# Power.net
KiCad netlist of a schematic drawn in Altium Designer
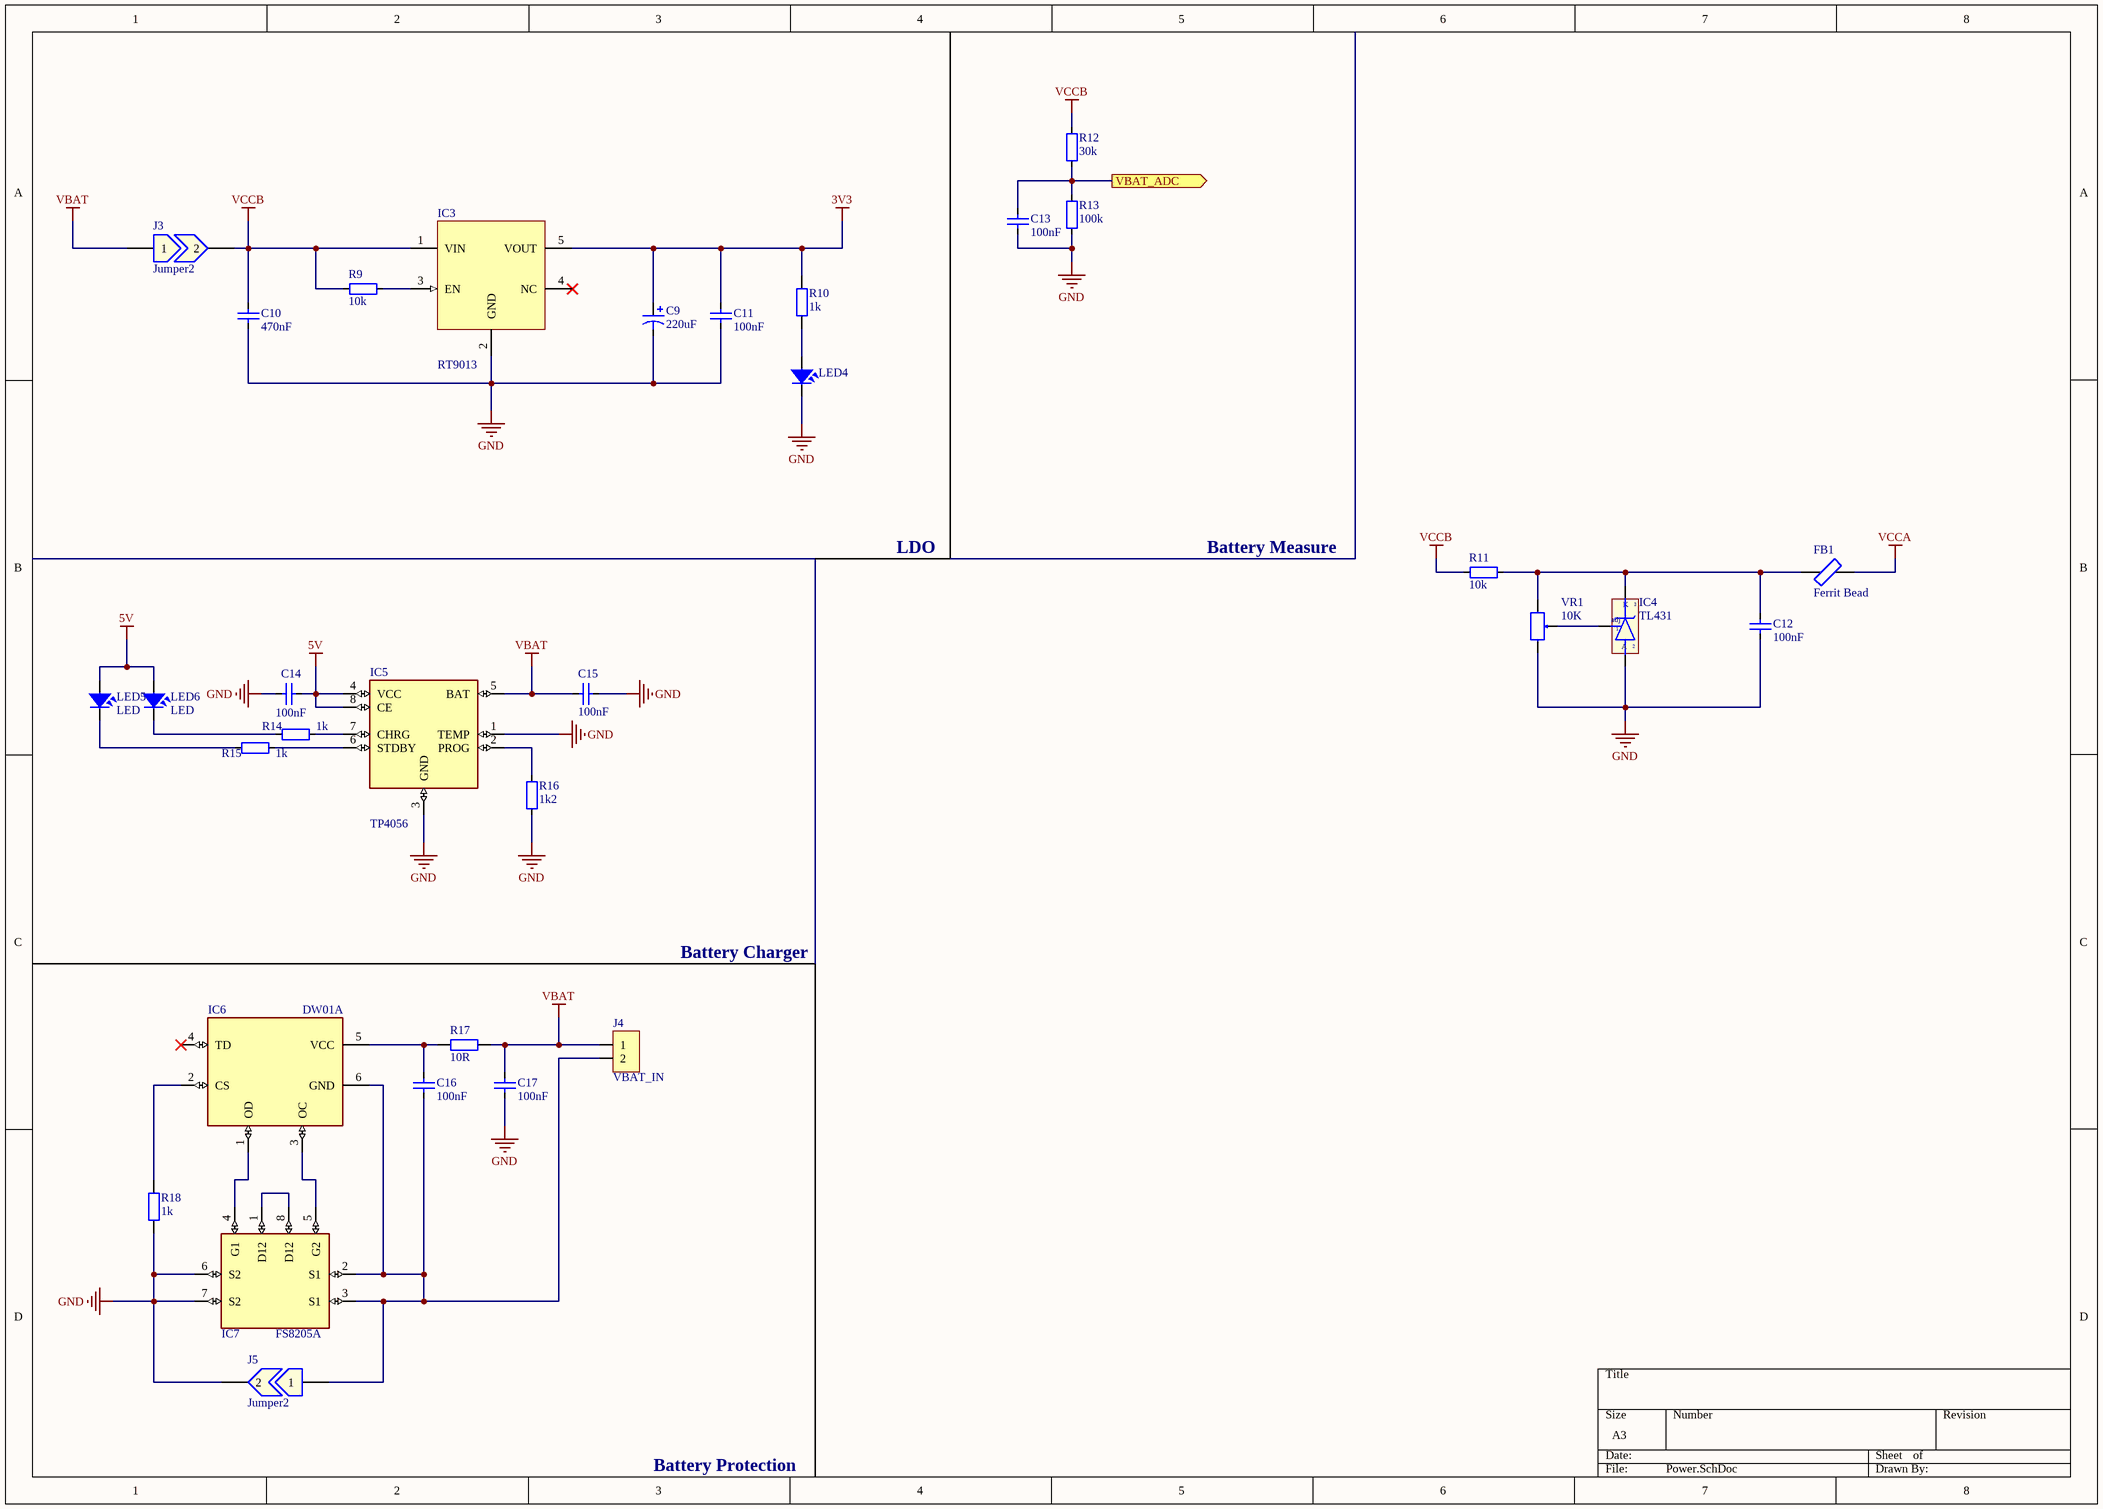
[diagram p0: Power.SchDoc]

(export (version "E")
  (design (tool "Eeschema 10.0.6"))
  (components
    (comp (ref "C9")
      (value "220uF")
      (footprint "CAP_TANTALUM_3216")
      (description "Polarized Capacitor (Axial)")
      (fields (field (name "PUBLISHER") "Altium Limited"))
      (libsource (lib "My Library") (part "Cap Pol"))
    )
    (comp (ref "C10")
      (value "470nF")
      (footprint "CAP_0805")
      (description "Capacitor")
      (fields (field (name "PUBLISHER") "Altium Limited"))
      (libsource (lib "My Library") (part "CapSMD"))
    )
    (comp (ref "C11")
      (value "100nF")
      (footprint "CAP_0805")
      (description "Capacitor")
      (fields (field (name "PUBLISHER") "Altium Limited"))
      (libsource (lib "My Library") (part "CapSMD"))
    )
    (comp (ref "C12")
      (value "100nF")
      (footprint "CAP_0805")
      (description "Capacitor")
      (fields (field (name "PUBLISHER") "Altium Limited"))
      (libsource (lib "My Library") (part "CapSMD"))
    )
    (comp (ref "C13")
      (value "100nF")
      (footprint "CAP_0805")
      (description "Capacitor")
      (fields (field (name "PUBLISHER") "Altium Limited"))
      (libsource (lib "My Library") (part "CapSMD"))
    )
    (comp (ref "C14")
      (value "100nF")
      (footprint "CAP_0805")
      (description "Capacitor")
      (fields (field (name "PUBLISHER") "Altium Limited"))
      (libsource (lib "My Library") (part "CapSMD"))
    )
    (comp (ref "C15")
      (value "100nF")
      (footprint "CAP_0805")
      (description "Capacitor")
      (fields (field (name "PUBLISHER") "Altium Limited"))
      (libsource (lib "My Library") (part "CapSMD"))
    )
    (comp (ref "C16")
      (value "100nF")
      (footprint "CAP_0805")
      (description "Capacitor")
      (fields (field (name "PUBLISHER") "Altium Limited"))
      (libsource (lib "My Library") (part "CapSMD"))
    )
    (comp (ref "C17")
      (value "100nF")
      (footprint "CAP_0805")
      (description "Capacitor")
      (fields (field (name "PUBLISHER") "Altium Limited"))
      (libsource (lib "My Library") (part "CapSMD"))
    )
    (comp (ref "FB1")
      (value "Ferrit Bead")
      (footprint "RES-SMD-0805")
      (description "Generic Ferrit Bead")
      (libsource (lib "My Library") (part "Ferrit Bead"))
    )
    (comp (ref "IC3")
      (value "RT9013")
      (footprint "SOT23-5")
      (description "https://linhkien.cxt.vn/5435-rt9013-33gb-ic-reg-linear-33v-500ma-sot23-5.html")
      (libsource (lib "My Library") (part "RT9013"))
    )
    (comp (ref "IC4")
      (value "TL431")
      (footprint "qto-92")
      (description "Programmable Shunt Regulator")
      (libsource (lib "My Library") (part "TL431"))
    )
    (comp (ref "IC5")
      (value "TP4056")
      (footprint "TP4056")
      (description "Complete single cell Li-Ion battery with a constant current / constant voltage linear charger")
      (libsource (lib "My Library") (part "TP4056"))
    )
    (comp (ref "IC6")
      (value "DW01A")
      (footprint "SOT23-6")
      (description "One Cell Lithium-ion/Polymer Battery Protection IC")
      (libsource (lib "My Library") (part "DW01A"))
    )
    (comp (ref "IC7") (value "FS8205A") (footprint "FS8205A") (libsource (lib "My Library") (part "FS8205A")))
    (comp (ref "J3")
      (value "Jumper2")
      (footprint "JUMPER2")
      (description "Jumper, 2-Pin")
      (libsource (lib "Main") (part "Jumper2"))
    )
    (comp (ref "J4")
      (value "VBAT_IN")
      (footprint "JP2-D1T")
      (description "WR-PHD 2.54 mm Angled Socket Header")
      (fields
        (field (name "MANUFACTURER") "Würth Elektronik eiSos GmbH")
        (field (name "PARTNO") "613002143121")
        (field (name "CREATED BY") "Karrer Zheng")
      )
      (libsource (lib "My Library") (part "JP2"))
    )
    (comp (ref "J5")
      (value "Jumper2")
      (footprint "JUMPER2")
      (description "Jumper, 2-Pin")
      (libsource (lib "My Library") (part "Jumper2"))
    )
    (comp (ref "LED4")
      (value "~")
      (footprint "LED-0805-Red")
      (description "LED Single colour Green and Red")
      (libsource (lib "Main") (part "LED"))
    )
    (comp (ref "LED5")
      (value "LED")
      (footprint "LED-0805-Red")
      (description "LED Single colour Green and Red")
      (libsource (lib "My Library") (part "LED"))
    )
    (comp (ref "LED6")
      (value "LED")
      (footprint "LED-0805-Green")
      (description "LED Single colour Green and Red")
      (libsource (lib "My Library") (part "LED"))
    )
    (comp (ref "R9")
      (value "10k")
      (footprint "RES-SMD-0805")
      (description "Resistor")
      (fields
        (field (name "MANUFACTURER") "Generic Components")
        (field (name "PUBLISHER") "Altium Hobart Technology Centre")
      )
      (libsource (lib "My Library") (part "Resistor - SMD"))
    )
    (comp (ref "R10")
      (value "1k")
      (footprint "RES-SMD-0805")
      (description "Resistor SMD")
      (fields
        (field (name "MANUFACTURER") "Generic Components")
        (field (name "PUBLISHER") "Altium Hobart Technology Centre")
      )
      (libsource (lib "Main") (part "Resistor - SMD"))
    )
    (comp (ref "R11")
      (value "10k")
      (footprint "RES-SMD-0805")
      (description "Resistor")
      (fields
        (field (name "MANUFACTURER") "Generic Components")
        (field (name "PUBLISHER") "Altium Hobart Technology Centre")
      )
      (libsource (lib "My Library") (part "Resistor - SMD"))
    )
    (comp (ref "R12")
      (value "30k")
      (footprint "RES-SMD-0805")
      (description "Resistor")
      (fields
        (field (name "MANUFACTURER") "Generic Components")
        (field (name "PUBLISHER") "Altium Hobart Technology Centre")
      )
      (libsource (lib "My Library") (part "Resistor - SMD"))
    )
    (comp (ref "R13")
      (value "100k")
      (footprint "RES-SMD-0805")
      (description "Resistor")
      (fields
        (field (name "MANUFACTURER") "Generic Components")
        (field (name "PUBLISHER") "Altium Hobart Technology Centre")
      )
      (libsource (lib "My Library") (part "Resistor - SMD"))
    )
    (comp (ref "R14")
      (value "1k")
      (footprint "RES-SMD-0805")
      (description "Resistor")
      (fields
        (field (name "MANUFACTURER") "Generic Components")
        (field (name "PUBLISHER") "Altium Hobart Technology Centre")
      )
      (libsource (lib "My Library") (part "Resistor - SMD"))
    )
    (comp (ref "R15")
      (value "1k")
      (footprint "RES-SMD-0805")
      (description "Resistor")
      (fields
        (field (name "MANUFACTURER") "Generic Components")
        (field (name "PUBLISHER") "Altium Hobart Technology Centre")
      )
      (libsource (lib "My Library") (part "Resistor - SMD"))
    )
    (comp (ref "R16")
      (value "1k2")
      (footprint "RES-SMD-0805")
      (description "Resistor")
      (fields
        (field (name "MANUFACTURER") "Generic Components")
        (field (name "PUBLISHER") "Altium Hobart Technology Centre")
      )
      (libsource (lib "My Library") (part "Resistor - SMD"))
    )
    (comp (ref "R17")
      (value "10R")
      (footprint "RES-SMD-0805")
      (description "Resistor SMD")
      (fields
        (field (name "MANUFACTURER") "Generic Components")
        (field (name "PUBLISHER") "Altium Hobart Technology Centre")
      )
      (libsource (lib "") (part "Resistor - SMD_1"))
    )
    (comp (ref "R18")
      (value "1k")
      (footprint "RES-SMD-0805")
      (description "Resistor SMD")
      (fields
        (field (name "MANUFACTURER") "Generic Components")
        (field (name "PUBLISHER") "Altium Hobart Technology Centre")
      )
      (libsource (lib "") (part "Resistor - SMD_1"))
    )
    (comp (ref "VR1")
      (value "10K")
      (footprint "VR1")
      (description "Var Resistor")
      (libsource (lib "My Library") (part "VR"))
    )
  )
  (nets
    (net (code "1") (name "/VBAT_ADC") (class "Default")
      (node (ref "C13") (pin "2") (pinfunction "2_2") (pintype "passive"))
      (node (ref "R12") (pin "2") (pinfunction "2_2") (pintype "passive"))
      (node (ref "R13") (pin "1") (pinfunction "1_1") (pintype "passive"))
    )
    (net (code "2") (name "3V3") (class "Default")
      (node (ref "C11") (pin "1") (pinfunction "1_1") (pintype "passive"))
      (node (ref "C9") (pin "1") (pinfunction "1_1") (pintype "passive"))
      (node (ref "IC3") (pin "5") (pinfunction "VOUT_5") (pintype "power_in"))
      (node (ref "R10") (pin "2") (pinfunction "2_2") (pintype "passive"))
    )
    (net (code "3") (name "5V") (class "Default")
      (node (ref "C14") (pin "1") (pinfunction "1_1") (pintype "passive"))
      (node (ref "IC5") (pin "4") (pinfunction "VCC_4") (pintype "bidirectional"))
      (node (ref "IC5") (pin "8") (pinfunction "CE_8") (pintype "bidirectional"))
      (node (ref "LED5") (pin "1") (pinfunction "1_1") (pintype "passive"))
      (node (ref "LED6") (pin "1") (pinfunction "1_1") (pintype "passive"))
    )
    (net (code "4") (name "GND") (class "Default")
      (node (ref "C10") (pin "2") (pinfunction "2_2") (pintype "passive"))
      (node (ref "C11") (pin "2") (pinfunction "2_2") (pintype "passive"))
      (node (ref "C12") (pin "2") (pinfunction "2_2") (pintype "passive"))
      (node (ref "C13") (pin "1") (pinfunction "1_1") (pintype "passive"))
      (node (ref "C14") (pin "2") (pinfunction "2_2") (pintype "passive"))
      (node (ref "C15") (pin "1") (pinfunction "1_1") (pintype "passive"))
      (node (ref "C17") (pin "1") (pinfunction "1_1") (pintype "passive"))
      (node (ref "C9") (pin "2") (pinfunction "2_2") (pintype "passive"))
      (node (ref "IC3") (pin "2") (pinfunction "GND_2") (pintype "power_in"))
      (node (ref "IC4") (pin "2") (pinfunction "A_2") (pintype "passive"))
      (node (ref "IC5") (pin "1") (pinfunction "TEMP_1") (pintype "bidirectional"))
      (node (ref "IC5") (pin "3") (pinfunction "GND_3") (pintype "bidirectional"))
      (node (ref "IC7") (pin "6") (pinfunction "S2_6") (pintype "bidirectional"))
      (node (ref "IC7") (pin "7") (pinfunction "S2_7") (pintype "bidirectional"))
      (node (ref "J5") (pin "2") (pinfunction "2_2") (pintype "passive"))
      (node (ref "LED4") (pin "2") (pinfunction "2_2") (pintype "passive"))
      (node (ref "R13") (pin "2") (pinfunction "2_2") (pintype "passive"))
      (node (ref "R16") (pin "1") (pinfunction "1_1") (pintype "passive"))
      (node (ref "R18") (pin "2") (pinfunction "2_2") (pintype "passive"))
      (node (ref "VR1") (pin "3") (pinfunction "3_3") (pintype "passive"))
    )
    (net (code "5") (name "Net-(IC3-EN)") (class "Default")
      (node (ref "IC3") (pin "3") (pinfunction "EN_3") (pintype "input"))
      (node (ref "R9") (pin "1") (pinfunction "1_1") (pintype "passive"))
    )
    (net (code "6") (name "Net-(IC4-K)") (class "Default")
      (node (ref "C12") (pin "1") (pinfunction "1_1") (pintype "passive"))
      (node (ref "FB1") (pin "1") (pintype "passive"))
      (node (ref "IC4") (pin "3") (pinfunction "K_3") (pintype "passive"))
      (node (ref "R11") (pin "1") (pinfunction "1_1") (pintype "passive"))
      (node (ref "VR1") (pin "1") (pinfunction "1_1") (pintype "passive"))
    )
    (net (code "7") (name "Net-(IC4-adj)") (class "Default")
      (node (ref "IC4") (pin "1") (pinfunction "adj_1") (pintype "passive"))
      (node (ref "VR1") (pin "2") (pinfunction "2_2") (pintype "passive"))
    )
    (net (code "8") (name "Net-(IC5-CHRG)") (class "Default")
      (node (ref "IC5") (pin "7") (pinfunction "CHRG_7") (pintype "bidirectional"))
      (node (ref "R14") (pin "1") (pinfunction "1_1") (pintype "passive"))
    )
    (net (code "9") (name "Net-(IC5-PROG)") (class "Default")
      (node (ref "IC5") (pin "2") (pinfunction "PROG_2") (pintype "bidirectional"))
      (node (ref "R16") (pin "2") (pinfunction "2_2") (pintype "passive"))
    )
    (net (code "10") (name "Net-(IC5-STDBY)") (class "Default")
      (node (ref "IC5") (pin "6") (pinfunction "STDBY_6") (pintype "bidirectional"))
      (node (ref "R15") (pin "1") (pinfunction "1_1") (pintype "passive"))
    )
    (net (code "11") (name "Net-(IC6-CS)") (class "Default")
      (node (ref "IC6") (pin "2") (pinfunction "CS_2") (pintype "bidirectional"))
      (node (ref "R18") (pin "1") (pinfunction "1_1") (pintype "passive"))
    )
    (net (code "12") (name "Net-(IC6-GND)") (class "Default")
      (node (ref "C16") (pin "1") (pinfunction "1_1") (pintype "passive"))
      (node (ref "IC6") (pin "6") (pinfunction "GND_6") (pintype "power_in"))
      (node (ref "IC7") (pin "2") (pinfunction "S1_2") (pintype "bidirectional"))
      (node (ref "IC7") (pin "3") (pinfunction "S1_3") (pintype "bidirectional"))
      (node (ref "J4") (pin "2") (pinfunction "2_2") (pintype "passive"))
      (node (ref "J5") (pin "1") (pinfunction "1_1") (pintype "passive"))
    )
    (net (code "13") (name "Net-(IC6-OC)") (class "Default")
      (node (ref "IC6") (pin "3") (pinfunction "OC_3") (pintype "bidirectional"))
      (node (ref "IC7") (pin "5") (pinfunction "G2_5") (pintype "bidirectional"))
    )
    (net (code "14") (name "Net-(IC6-OD)") (class "Default")
      (node (ref "IC6") (pin "1") (pinfunction "OD_1") (pintype "bidirectional"))
      (node (ref "IC7") (pin "4") (pinfunction "G1_4") (pintype "bidirectional"))
    )
    (net (code "15") (name "Net-(IC6-VCC)") (class "Default")
      (node (ref "C16") (pin "2") (pinfunction "2_2") (pintype "passive"))
      (node (ref "IC6") (pin "5") (pinfunction "VCC_5") (pintype "power_in"))
      (node (ref "R17") (pin "1") (pinfunction "1_1") (pintype "passive"))
    )
    (net (code "16") (name "Net-(IC7-D12-Pad1)") (class "Default")
      (node (ref "IC7") (pin "1") (pinfunction "D12_1") (pintype "bidirectional"))
      (node (ref "IC7") (pin "8") (pinfunction "D12_8") (pintype "bidirectional"))
    )
    (net (code "17") (name "Net-(LED4-Pad1)") (class "Default")
      (node (ref "LED4") (pin "1") (pinfunction "1_1") (pintype "passive"))
      (node (ref "R10") (pin "1") (pinfunction "1_1") (pintype "passive"))
    )
    (net (code "18") (name "Net-(LED5-Pad2)") (class "Default")
      (node (ref "LED5") (pin "2") (pinfunction "2_2") (pintype "passive"))
      (node (ref "R15") (pin "2") (pinfunction "2_2") (pintype "passive"))
    )
    (net (code "19") (name "Net-(LED6-Pad2)") (class "Default")
      (node (ref "LED6") (pin "2") (pinfunction "2_2") (pintype "passive"))
      (node (ref "R14") (pin "2") (pinfunction "2_2") (pintype "passive"))
    )
    (net (code "20") (name "VBAT") (class "Default")
      (node (ref "C15") (pin "2") (pinfunction "2_2") (pintype "passive"))
      (node (ref "C17") (pin "2") (pinfunction "2_2") (pintype "passive"))
      (node (ref "IC5") (pin "5") (pinfunction "BAT_5") (pintype "bidirectional"))
      (node (ref "J3") (pin "1") (pinfunction "1_1") (pintype "passive"))
      (node (ref "J4") (pin "1") (pinfunction "1_1") (pintype "passive"))
      (node (ref "R17") (pin "2") (pinfunction "2_2") (pintype "passive"))
    )
    (net (code "21") (name "VCCA") (class "Default") (node (ref "FB1") (pin "2") (pintype "passive")))
    (net (code "22") (name "VCCB") (class "Default")
      (node (ref "C10") (pin "1") (pinfunction "1_1") (pintype "passive"))
      (node (ref "IC3") (pin "1") (pinfunction "VIN_1") (pintype "power_in"))
      (node (ref "J3") (pin "2") (pinfunction "2_2") (pintype "passive"))
      (node (ref "R11") (pin "2") (pinfunction "2_2") (pintype "passive"))
      (node (ref "R12") (pin "1") (pinfunction "1_1") (pintype "passive"))
      (node (ref "R9") (pin "2") (pinfunction "2_2") (pintype "passive"))
    )
    (net (code "23") (name "unconnected-(IC3-NC-Pad4)") (class "Default")
      (node (ref "IC3") (pin "4") (pinfunction "NC_4") (pintype "passive+no_connect"))
    )
    (net (code "24") (name "unconnected-(IC6-TD-Pad4)") (class "Default")
      (node (ref "IC6") (pin "4") (pinfunction "TD_4") (pintype "bidirectional+no_connect"))
    )
  )
)
